# Vsense_Thermistor.net
KiCad netlist of a schematic drawn in Altium Designer
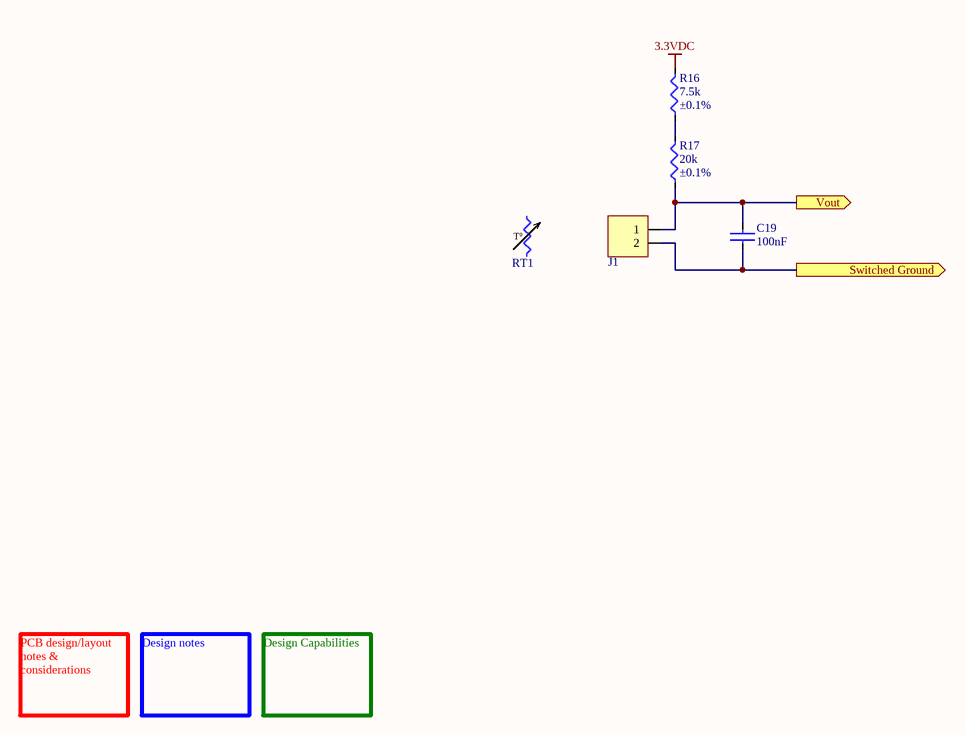
[diagram p0: Vsense Thermistor.SchDoc]

(export (version "E")
  (design (tool "Eeschema 10.0.6"))
  (components
    (comp (ref "C19")
      (value "100nF 0603 50V")
      (footprint "C0603 - Ceramic")
      (fields
        (field (name "MANUFACTURER") "Samsung Electro-Mechanics America, Inc")
        (field (name "MANUFACTURER PART NUMBER") "CL10B104KB8SFNC")
        (field (name "TOLERANCE") "±10%")
        (field (name "CAPACITANCE") "100nF")
      )
      (libsource (lib "Personal Library") (part "100nF 0603 50V"))
    )
    (comp (ref "J1")
      (value "Tº")
      (fields
        (field (name "MANUFACTURER") "TE Connectivity AMP Connectors")
        (field (name "MANUFACTURER PART NUMBER") "640456-2")
      )
      (libsource (lib "Local Library") (part "MTA100-2 with friction Lock"))
    )
    (comp (ref "R16")
      (value "7.5k 0603 0.1%")
      (footprint "R0603")
      (description "Resistor")
      (fields
        (field (name "MANUFACTURER") "Yageo")
        (field (name "MANUFACTURER PART NUMBER") "RT0603BRD077K5L")
        (field (name "RESISTANCE (OHMS)") "7.5k")
        (field (name "TOLERANCE") "±0.1%")
      )
      (libsource (lib "Local Library") (part "7.5k 0603 0.1%"))
    )
    (comp (ref "R17")
      (value "20k 0603 0.1%")
      (footprint "R0603")
      (description "Resistor")
      (fields
        (field (name "MANUFACTURER") "Yageo")
        (field (name "MANUFACTURER PART NUMBER") "RT0603BRD0720KL")
        (field (name "RESISTANCE (OHMS)") "20k")
        (field (name "TOLERANCE") "±0.1%")
      )
      (libsource (lib "Local Library") (part "20k 0603 0.1%"))
    )
    (comp (ref "RT1")
      (value "Tº")
      (footprint "Connector - MTA-100 2 Position Friction Lock")
      (description "Resistor")
      (fields
        (field (name "MANUFACTURER") "Murata Electronics North America")
        (field (name "MANUFACTURER PART NUMBER") "NXFT15XH103FA2B025")
      )
      (libsource (lib "Local Library") (part "Thermistor 10k Type J"))
    )
  )
  (nets
    (net (code "1") (name "/Switched Ground") (class "Default")
      (node (ref "C19") (pin "2") (pinfunction "2_2") (pintype "passive"))
      (node (ref "J1") (pin "2") (pinfunction "2_2") (pintype "passive"))
    )
    (net (code "2") (name "/Vout") (class "Default")
      (node (ref "C19") (pin "1") (pinfunction "1_1") (pintype "passive"))
      (node (ref "J1") (pin "1") (pinfunction "1_1") (pintype "passive"))
      (node (ref "R17") (pin "2") (pinfunction "2_2") (pintype "passive"))
    )
    (net (code "3") (name "3.3VDC") (class "Default")
      (node (ref "R16") (pin "1") (pinfunction "1_1") (pintype "passive"))
    )
    (net (code "4") (name "Net-(R16-Pad2)") (class "Default")
      (node (ref "R16") (pin "2") (pinfunction "2_2") (pintype "passive"))
      (node (ref "R17") (pin "1") (pinfunction "1_1") (pintype "passive"))
    )
  )
)
